# trezor_diy_dev.net
KiCad netlist of a schematic drawn in EAGLE
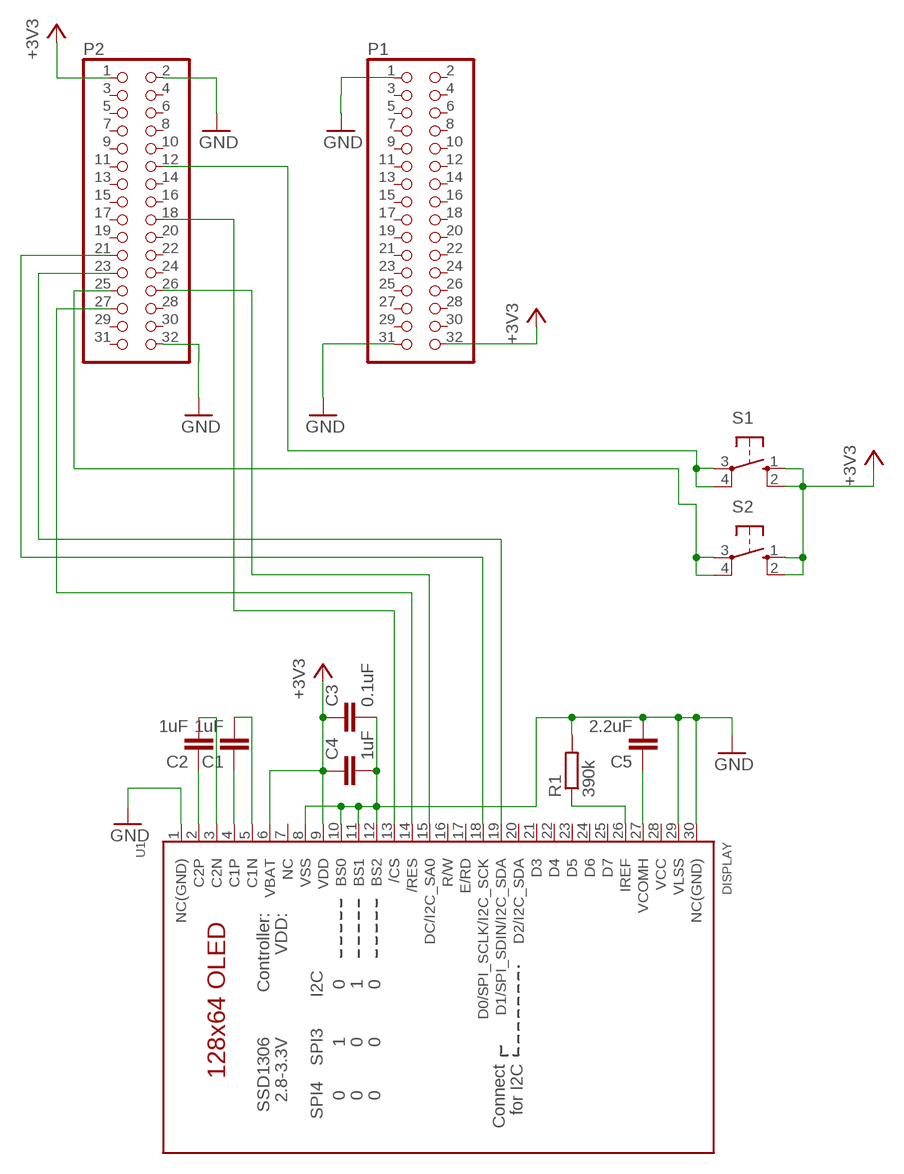
[diagram p0: schematic, sheet 1]

(export (version "E")
  (design (tool "Eeschema 10.0.6"))
  (components
    (comp (ref "C1")
      (value "1uF")
      (footprint "eagle-import:C5B2.5")
      (libsource (lib "eagle-import") (part "C5/2.5"))
    )
    (comp (ref "C2")
      (value "1uF")
      (footprint "eagle-import:C5B2.5")
      (libsource (lib "eagle-import") (part "C5/2.5"))
    )
    (comp (ref "C3")
      (value "0.1uF")
      (footprint "eagle-import:C5B2.5")
      (libsource (lib "eagle-import") (part "C5/2.5"))
    )
    (comp (ref "C4")
      (value "1uF")
      (footprint "eagle-import:C5B2.5")
      (libsource (lib "eagle-import") (part "C5/2.5"))
    )
    (comp (ref "C5")
      (value "2.2uF")
      (footprint "eagle-import:C5B2.5")
      (libsource (lib "eagle-import") (part "C5/2.5"))
    )
    (comp (ref "P1")
      (value "PINHD-2X16")
      (footprint "eagle-import:2X16")
      (libsource (lib "eagle-import") (part "PINHD-2X16"))
    )
    (comp (ref "P2")
      (value "PINHD-2X16")
      (footprint "eagle-import:2X16")
      (libsource (lib "eagle-import") (part "PINHD-2X16"))
    )
    (comp (ref "R1")
      (value "390k")
      (footprint "eagle-import:0309_10")
      (libsource (lib "eagle-import") (part "R-EU_0309/10"))
    )
    (comp (ref "S1")
      (value "10-XX")
      (footprint "eagle-import:B3F-10XX")
      (fields (field (name "MPN") "B3F-1000"))
      (libsource (lib "eagle-import") (part "10-XX"))
    )
    (comp (ref "S2")
      (value "10-XX")
      (footprint "eagle-import:B3F-10XX")
      (fields (field (name "MPN") "B3F-1000"))
      (libsource (lib "eagle-import") (part "10-XX"))
    )
    (comp (ref "U1")
      (value "DISPLAY")
      (footprint "eagle-import:UG-2864HSWEG01_0.96IN_WRAPAROUND")
      (libsource (lib "eagle-import") (part "DISP_OLED_UG-2864HSWEG010.96{dblquote}"))
    )
  )
  (nets
    (net (code "1") (name "+3V3") (class "Default")
      (node (ref "C3") (pin "1") (pinfunction "1_1") (pintype "passive"))
      (node (ref "C4") (pin "1") (pinfunction "1_1") (pintype "passive"))
      (node (ref "P1") (pin "32") (pinfunction "32_32") (pintype "passive"))
      (node (ref "P2") (pin "1") (pinfunction "1_1") (pintype "passive"))
      (node (ref "S1") (pin "1") (pinfunction "S_1") (pintype "passive"))
      (node (ref "S1") (pin "2") (pinfunction "S1_2") (pintype "passive"))
      (node (ref "S2") (pin "1") (pinfunction "S_1") (pintype "passive"))
      (node (ref "S2") (pin "2") (pinfunction "S1_2") (pintype "passive"))
      (node (ref "U1") (pin "6") (pinfunction "VBAT_6") (pintype "input"))
      (node (ref "U1") (pin "9") (pinfunction "VDD_9") (pintype "power_in"))
    )
    (net (code "2") (name "/VCC") (class "Default")
      (node (ref "U1") (pin "28") (pinfunction "VCC_28") (pintype "power_in"))
    )
    (net (code "3") (name "GND") (class "Default")
      (node (ref "C3") (pin "2") (pinfunction "2_2") (pintype "passive"))
      (node (ref "C4") (pin "2") (pinfunction "2_2") (pintype "passive"))
      (node (ref "C5") (pin "2") (pinfunction "2_2") (pintype "passive"))
      (node (ref "P1") (pin "1") (pinfunction "1_1") (pintype "passive"))
      (node (ref "P1") (pin "31") (pinfunction "31_31") (pintype "passive"))
      (node (ref "P2") (pin "2") (pinfunction "2_2") (pintype "passive"))
      (node (ref "P2") (pin "32") (pinfunction "32_32") (pintype "passive"))
      (node (ref "R1") (pin "2") (pinfunction "2_2") (pintype "passive"))
      (node (ref "U1") (pin "1") (pinfunction "NC(GND)_1") (pintype "input"))
      (node (ref "U1") (pin "10") (pinfunction "BS0_10") (pintype "input"))
      (node (ref "U1") (pin "11") (pinfunction "BS1_11") (pintype "input"))
      (node (ref "U1") (pin "12") (pinfunction "BS2_12") (pintype "input"))
      (node (ref "U1") (pin "29") (pinfunction "VLSS_29") (pintype "power_in"))
      (node (ref "U1") (pin "30") (pinfunction "NC(GND)_30") (pintype "input"))
      (node (ref "U1") (pin "8") (pinfunction "VSS_8") (pintype "power_in"))
    )
    (net (code "4") (name "Net-(S1-P)") (class "Default")
      (node (ref "P2") (pin "12") (pinfunction "12_12") (pintype "passive"))
      (node (ref "S1") (pin "3") (pinfunction "P_3") (pintype "passive"))
      (node (ref "S1") (pin "4") (pinfunction "P1_4") (pintype "passive"))
    )
    (net (code "5") (name "Net-(S2-P)") (class "Default")
      (node (ref "P2") (pin "25") (pinfunction "25_25") (pintype "passive"))
      (node (ref "S2") (pin "3") (pinfunction "P_3") (pintype "passive"))
      (node (ref "S2") (pin "4") (pinfunction "P1_4") (pintype "passive"))
    )
    (net (code "6") (name "Net-(U1-C1N)") (class "Default")
      (node (ref "C1") (pin "2") (pinfunction "2_2") (pintype "passive"))
      (node (ref "U1") (pin "5") (pinfunction "C1N_5") (pintype "input"))
    )
    (net (code "7") (name "Net-(U1-C1P)") (class "Default")
      (node (ref "C1") (pin "1") (pinfunction "1_1") (pintype "passive"))
      (node (ref "U1") (pin "4") (pinfunction "C1P_4") (pintype "input"))
    )
    (net (code "8") (name "Net-(U1-C2N)") (class "Default")
      (node (ref "C2") (pin "2") (pinfunction "2_2") (pintype "passive"))
      (node (ref "U1") (pin "3") (pinfunction "C2N_3") (pintype "input"))
    )
    (net (code "9") (name "Net-(U1-C2P)") (class "Default")
      (node (ref "C2") (pin "1") (pinfunction "1_1") (pintype "passive"))
      (node (ref "U1") (pin "2") (pinfunction "C2P_2") (pintype "input"))
    )
    (net (code "10") (name "Net-(U1-D0{slash}SPI_SCLK{slash}I2C_SCK)") (class "Default")
      (node (ref "P2") (pin "21") (pinfunction "21_21") (pintype "passive"))
      (node (ref "U1") (pin "18") (pinfunction "D0/SPI_SCLK/I2C_SCK_18") (pintype "bidirectional"))
    )
    (net (code "11") (name "Net-(U1-D1{slash}SPI_SDIN{slash}I2C_SDA)") (class "Default")
      (node (ref "P2") (pin "23") (pinfunction "23_23") (pintype "passive"))
      (node (ref "U1") (pin "19") (pinfunction "D1/SPI_SDIN/I2C_SDA_19") (pintype "bidirectional"))
    )
    (net (code "12") (name "Net-(U1-DC{slash}I2C_SA0)") (class "Default")
      (node (ref "P2") (pin "26") (pinfunction "26_26") (pintype "passive"))
      (node (ref "U1") (pin "15") (pinfunction "DC/I2C_SA0_15") (pintype "input"))
    )
    (net (code "13") (name "Net-(U1-IREF)") (class "Default")
      (node (ref "R1") (pin "1") (pinfunction "1_1") (pintype "passive"))
      (node (ref "U1") (pin "26") (pinfunction "IREF_26") (pintype "input"))
    )
    (net (code "14") (name "Net-(U1-VCOMH)") (class "Default")
      (node (ref "C5") (pin "1") (pinfunction "1_1") (pintype "passive"))
      (node (ref "U1") (pin "27") (pinfunction "VCOMH_27") (pintype "output"))
    )
    (net (code "15") (name "Net-(U1-{slash}CS)") (class "Default")
      (node (ref "P2") (pin "18") (pinfunction "18_18") (pintype "passive"))
      (node (ref "U1") (pin "13") (pinfunction "/CS_13") (pintype "input"))
    )
    (net (code "16") (name "Net-(U1-{slash}RES)") (class "Default")
      (node (ref "P2") (pin "27") (pinfunction "27_27") (pintype "passive"))
      (node (ref "U1") (pin "14") (pinfunction "/RES_14") (pintype "input"))
    )
    (net (code "17") (name "unconnected-(P1-Pad2)") (class "Default")
      (node (ref "P1") (pin "2") (pinfunction "2_2") (pintype "passive"))
    )
    (net (code "18") (name "unconnected-(P1-Pad3)") (class "Default")
      (node (ref "P1") (pin "3") (pinfunction "3_3") (pintype "passive"))
    )
    (net (code "19") (name "unconnected-(P1-Pad4)") (class "Default")
      (node (ref "P1") (pin "4") (pinfunction "4_4") (pintype "passive"))
    )
    (net (code "20") (name "unconnected-(P1-Pad5)") (class "Default")
      (node (ref "P1") (pin "5") (pinfunction "5_5") (pintype "passive"))
    )
    (net (code "21") (name "unconnected-(P1-Pad6)") (class "Default")
      (node (ref "P1") (pin "6") (pinfunction "6_6") (pintype "passive"))
    )
    (net (code "22") (name "unconnected-(P1-Pad7)") (class "Default")
      (node (ref "P1") (pin "7") (pinfunction "7_7") (pintype "passive"))
    )
    (net (code "23") (name "unconnected-(P1-Pad8)") (class "Default")
      (node (ref "P1") (pin "8") (pinfunction "8_8") (pintype "passive"))
    )
    (net (code "24") (name "unconnected-(P1-Pad9)") (class "Default")
      (node (ref "P1") (pin "9") (pinfunction "9_9") (pintype "passive"))
    )
    (net (code "25") (name "unconnected-(P1-Pad10)") (class "Default")
      (node (ref "P1") (pin "10") (pinfunction "10_10") (pintype "passive"))
    )
    (net (code "26") (name "unconnected-(P1-Pad11)") (class "Default")
      (node (ref "P1") (pin "11") (pinfunction "11_11") (pintype "passive"))
    )
    (net (code "27") (name "unconnected-(P1-Pad12)") (class "Default")
      (node (ref "P1") (pin "12") (pinfunction "12_12") (pintype "passive"))
    )
    (net (code "28") (name "unconnected-(P1-Pad13)") (class "Default")
      (node (ref "P1") (pin "13") (pinfunction "13_13") (pintype "passive"))
    )
    (net (code "29") (name "unconnected-(P1-Pad14)") (class "Default")
      (node (ref "P1") (pin "14") (pinfunction "14_14") (pintype "passive"))
    )
    (net (code "30") (name "unconnected-(P1-Pad15)") (class "Default")
      (node (ref "P1") (pin "15") (pinfunction "15_15") (pintype "passive"))
    )
    (net (code "31") (name "unconnected-(P1-Pad16)") (class "Default")
      (node (ref "P1") (pin "16") (pinfunction "16_16") (pintype "passive"))
    )
    (net (code "32") (name "unconnected-(P1-Pad17)") (class "Default")
      (node (ref "P1") (pin "17") (pinfunction "17_17") (pintype "passive"))
    )
    (net (code "33") (name "unconnected-(P1-Pad18)") (class "Default")
      (node (ref "P1") (pin "18") (pinfunction "18_18") (pintype "passive"))
    )
    (net (code "34") (name "unconnected-(P1-Pad19)") (class "Default")
      (node (ref "P1") (pin "19") (pinfunction "19_19") (pintype "passive"))
    )
    (net (code "35") (name "unconnected-(P1-Pad20)") (class "Default")
      (node (ref "P1") (pin "20") (pinfunction "20_20") (pintype "passive"))
    )
    (net (code "36") (name "unconnected-(P1-Pad21)") (class "Default")
      (node (ref "P1") (pin "21") (pinfunction "21_21") (pintype "passive"))
    )
    (net (code "37") (name "unconnected-(P1-Pad22)") (class "Default")
      (node (ref "P1") (pin "22") (pinfunction "22_22") (pintype "passive"))
    )
    (net (code "38") (name "unconnected-(P1-Pad23)") (class "Default")
      (node (ref "P1") (pin "23") (pinfunction "23_23") (pintype "passive"))
    )
    (net (code "39") (name "unconnected-(P1-Pad24)") (class "Default")
      (node (ref "P1") (pin "24") (pinfunction "24_24") (pintype "passive"))
    )
    (net (code "40") (name "unconnected-(P1-Pad25)") (class "Default")
      (node (ref "P1") (pin "25") (pinfunction "25_25") (pintype "passive"))
    )
    (net (code "41") (name "unconnected-(P1-Pad26)") (class "Default")
      (node (ref "P1") (pin "26") (pinfunction "26_26") (pintype "passive"))
    )
    (net (code "42") (name "unconnected-(P1-Pad27)") (class "Default")
      (node (ref "P1") (pin "27") (pinfunction "27_27") (pintype "passive"))
    )
    (net (code "43") (name "unconnected-(P1-Pad28)") (class "Default")
      (node (ref "P1") (pin "28") (pinfunction "28_28") (pintype "passive"))
    )
    (net (code "44") (name "unconnected-(P1-Pad29)") (class "Default")
      (node (ref "P1") (pin "29") (pinfunction "29_29") (pintype "passive"))
    )
    (net (code "45") (name "unconnected-(P1-Pad30)") (class "Default")
      (node (ref "P1") (pin "30") (pinfunction "30_30") (pintype "passive"))
    )
    (net (code "46") (name "unconnected-(P2-Pad3)") (class "Default")
      (node (ref "P2") (pin "3") (pinfunction "3_3") (pintype "passive"))
    )
    (net (code "47") (name "unconnected-(P2-Pad4)") (class "Default")
      (node (ref "P2") (pin "4") (pinfunction "4_4") (pintype "passive"))
    )
    (net (code "48") (name "unconnected-(P2-Pad5)") (class "Default")
      (node (ref "P2") (pin "5") (pinfunction "5_5") (pintype "passive"))
    )
    (net (code "49") (name "unconnected-(P2-Pad6)") (class "Default")
      (node (ref "P2") (pin "6") (pinfunction "6_6") (pintype "passive"))
    )
    (net (code "50") (name "unconnected-(P2-Pad7)") (class "Default")
      (node (ref "P2") (pin "7") (pinfunction "7_7") (pintype "passive"))
    )
    (net (code "51") (name "unconnected-(P2-Pad8)") (class "Default")
      (node (ref "P2") (pin "8") (pinfunction "8_8") (pintype "passive"))
    )
    (net (code "52") (name "unconnected-(P2-Pad9)") (class "Default")
      (node (ref "P2") (pin "9") (pinfunction "9_9") (pintype "passive"))
    )
    (net (code "53") (name "unconnected-(P2-Pad10)") (class "Default")
      (node (ref "P2") (pin "10") (pinfunction "10_10") (pintype "passive"))
    )
    (net (code "54") (name "unconnected-(P2-Pad11)") (class "Default")
      (node (ref "P2") (pin "11") (pinfunction "11_11") (pintype "passive"))
    )
    (net (code "55") (name "unconnected-(P2-Pad13)") (class "Default")
      (node (ref "P2") (pin "13") (pinfunction "13_13") (pintype "passive"))
    )
    (net (code "56") (name "unconnected-(P2-Pad14)") (class "Default")
      (node (ref "P2") (pin "14") (pinfunction "14_14") (pintype "passive"))
    )
    (net (code "57") (name "unconnected-(P2-Pad15)") (class "Default")
      (node (ref "P2") (pin "15") (pinfunction "15_15") (pintype "passive"))
    )
    (net (code "58") (name "unconnected-(P2-Pad16)") (class "Default")
      (node (ref "P2") (pin "16") (pinfunction "16_16") (pintype "passive"))
    )
    (net (code "59") (name "unconnected-(P2-Pad17)") (class "Default")
      (node (ref "P2") (pin "17") (pinfunction "17_17") (pintype "passive"))
    )
    (net (code "60") (name "unconnected-(P2-Pad19)") (class "Default")
      (node (ref "P2") (pin "19") (pinfunction "19_19") (pintype "passive"))
    )
    (net (code "61") (name "unconnected-(P2-Pad20)") (class "Default")
      (node (ref "P2") (pin "20") (pinfunction "20_20") (pintype "passive"))
    )
    (net (code "62") (name "unconnected-(P2-Pad22)") (class "Default")
      (node (ref "P2") (pin "22") (pinfunction "22_22") (pintype "passive"))
    )
    (net (code "63") (name "unconnected-(P2-Pad24)") (class "Default")
      (node (ref "P2") (pin "24") (pinfunction "24_24") (pintype "passive"))
    )
    (net (code "64") (name "unconnected-(P2-Pad28)") (class "Default")
      (node (ref "P2") (pin "28") (pinfunction "28_28") (pintype "passive"))
    )
    (net (code "65") (name "unconnected-(P2-Pad29)") (class "Default")
      (node (ref "P2") (pin "29") (pinfunction "29_29") (pintype "passive"))
    )
    (net (code "66") (name "unconnected-(P2-Pad30)") (class "Default")
      (node (ref "P2") (pin "30") (pinfunction "30_30") (pintype "passive"))
    )
    (net (code "67") (name "unconnected-(P2-Pad31)") (class "Default")
      (node (ref "P2") (pin "31") (pinfunction "31_31") (pintype "passive"))
    )
    (net (code "68") (name "unconnected-(U1-D2{slash}I2C_SDA-Pad20)") (class "Default")
      (node (ref "U1") (pin "20") (pinfunction "D2/I2C_SDA_20") (pintype "bidirectional"))
    )
    (net (code "69") (name "unconnected-(U1-D3-Pad21)") (class "Default")
      (node (ref "U1") (pin "21") (pinfunction "D3_21") (pintype "bidirectional"))
    )
    (net (code "70") (name "unconnected-(U1-D4-Pad22)") (class "Default")
      (node (ref "U1") (pin "22") (pinfunction "D4_22") (pintype "bidirectional"))
    )
    (net (code "71") (name "unconnected-(U1-D5-Pad23)") (class "Default")
      (node (ref "U1") (pin "23") (pinfunction "D5_23") (pintype "bidirectional"))
    )
    (net (code "72") (name "unconnected-(U1-D6-Pad24)") (class "Default")
      (node (ref "U1") (pin "24") (pinfunction "D6_24") (pintype "bidirectional"))
    )
    (net (code "73") (name "unconnected-(U1-D7-Pad25)") (class "Default")
      (node (ref "U1") (pin "25") (pinfunction "D7_25") (pintype "bidirectional"))
    )
    (net (code "74") (name "unconnected-(U1-E{slash}RD-Pad17)") (class "Default")
      (node (ref "U1") (pin "17") (pinfunction "E/RD_17") (pintype "input"))
    )
    (net (code "75") (name "unconnected-(U1-NC-Pad7)") (class "Default")
      (node (ref "U1") (pin "7") (pinfunction "NC_7") (pintype "no_connect"))
    )
    (net (code "76") (name "unconnected-(U1-R{slash}W-Pad16)") (class "Default")
      (node (ref "U1") (pin "16") (pinfunction "R/W_16") (pintype "input"))
    )
  )
)
